# SCH_noobie-NFC_2024-11-30.net
KiCad netlist of a schematic drawn in EasyEDA
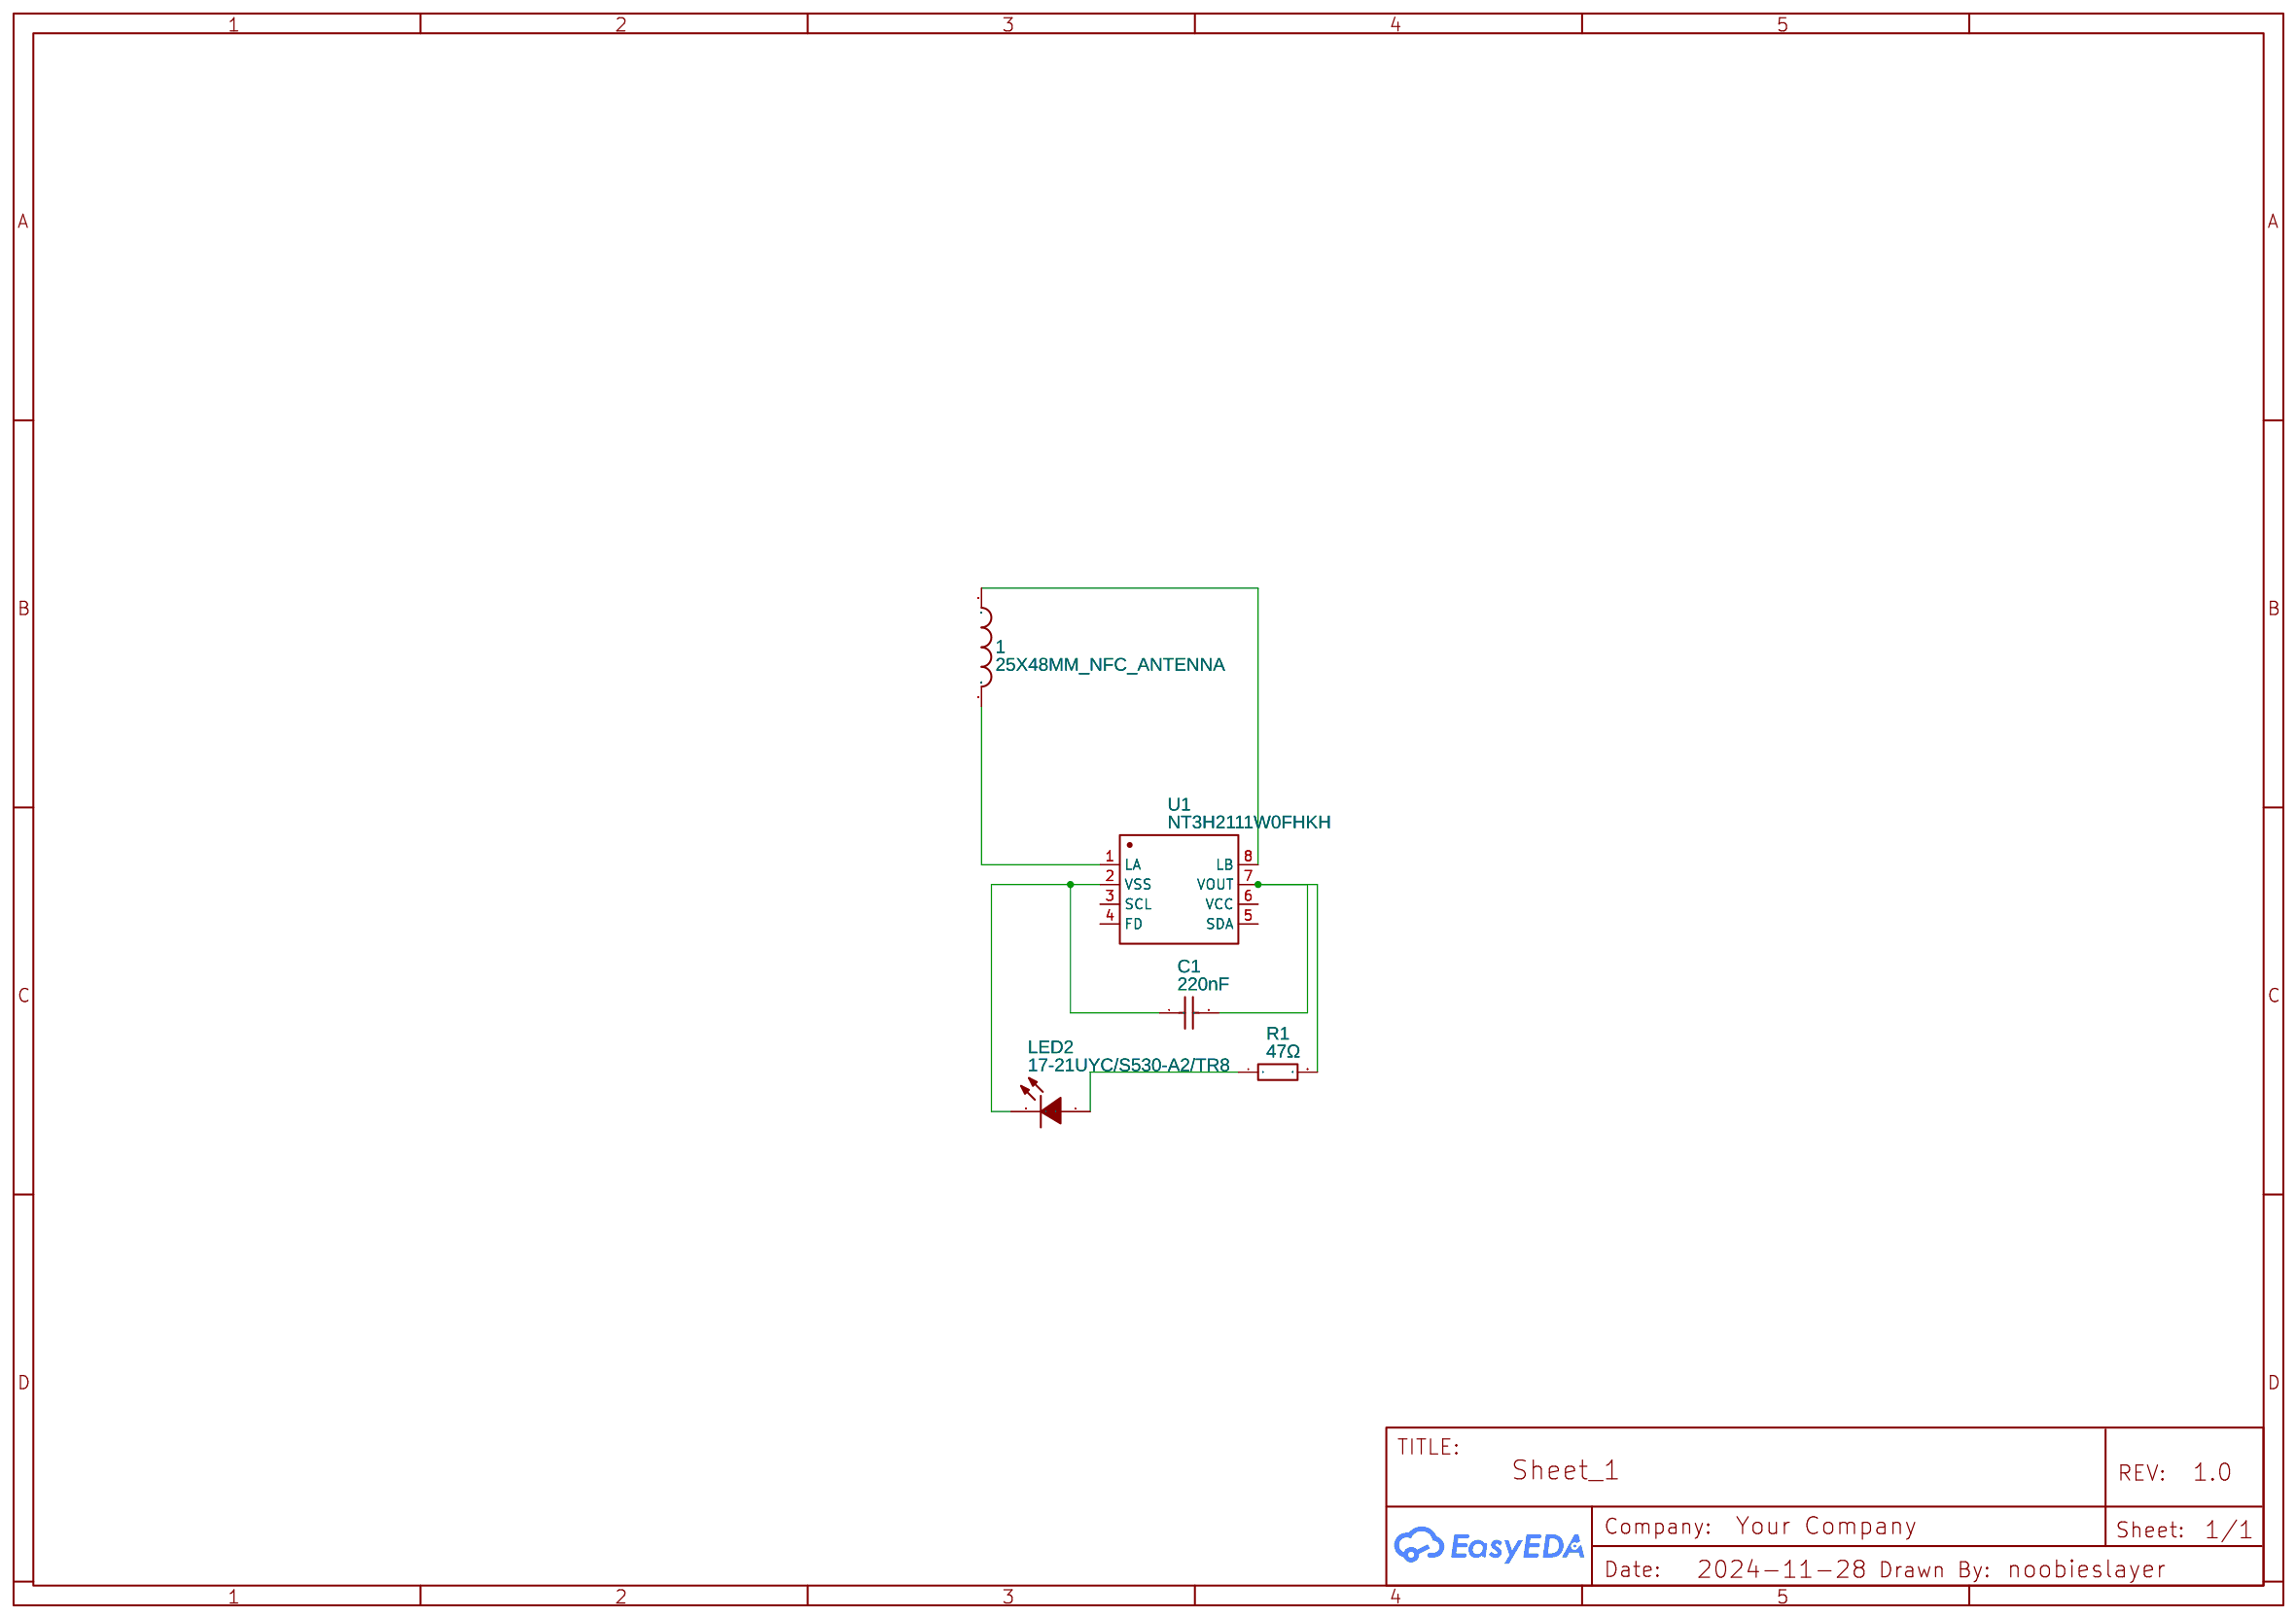
[diagram p0: schematic sheet]

(export (version "E")
  (design (tool "Eeschema 10.0.6"))
  (components
    (comp (ref "1") (value "25X48MM_NFC_ANTENNA") (libsource (lib "") (part "25X48MM_NFC_ANTENNA")))
    (comp (ref "C1")
      (value "220nF")
      (fields
        (field (name "Manufacturer Part") "CL10B224KA8NNNC")
        (field (name "Manufacturer") "SAMSUNG(三星)")
      )
      (libsource (lib "") (part "CL10B224KA8NNNC"))
    )
    (comp (ref "LED2")
      (value "17-21UYC/S530-A2/TR8")
      (fields (field (name "Manufacturer") "EVERLIGHT(亿光)"))
      (libsource (lib "") (part "17-21UYC/S530-A2/TR8"))
    )
    (comp (ref "R1")
      (value "47Ω")
      (fields
        (field (name "Manufacturer Part") "0603WAF470JT5E")
        (field (name "Manufacturer") "UNI-ROYAL(厚声)")
      )
      (libsource (lib "") (part "0603WAF470JT5E"))
    )
    (comp (ref "U1")
      (value "NT3H2111W0FHKH")
      (fields (field (name "Manufacturer") "NXP(恩智浦)"))
      (libsource (lib "") (part "NT3H2111W0FHKH"))
    )
  )
  (nets
    (net (code "1") (name "Net-(LED2-+)") (class "Default")
      (node (ref "LED2") (pin "1") (pinfunction "+_1") (pintype "unspecified"))
      (node (ref "R1") (pin "1") (pinfunction "1_1") (pintype "input"))
    )
    (net (code "2") (name "Net-(LED2--)") (class "Default")
      (node (ref "C1") (pin "1") (pinfunction "1_1") (pintype "input"))
      (node (ref "LED2") (pin "2") (pinfunction "-_2") (pintype "unspecified"))
      (node (ref "U1") (pin "2") (pinfunction "VSS_2") (pintype "unspecified"))
    )
    (net (code "3") (name "Net-(U1-LA)") (class "Default")
      (node (ref "1") (pin "P$2") (pinfunction "P$2_P$2") (pintype "bidirectional"))
      (node (ref "U1") (pin "1") (pinfunction "LA_1") (pintype "unspecified"))
    )
    (net (code "4") (name "Net-(U1-LB)") (class "Default")
      (node (ref "1") (pin "P$1") (pinfunction "P$1_P$1") (pintype "bidirectional"))
      (node (ref "U1") (pin "8") (pinfunction "LB_8") (pintype "unspecified"))
    )
    (net (code "5") (name "Net-(U1-VOUT)") (class "Default")
      (node (ref "C1") (pin "2") (pinfunction "2_2") (pintype "input"))
      (node (ref "R1") (pin "2") (pinfunction "2_2") (pintype "input"))
      (node (ref "U1") (pin "7") (pinfunction "VOUT_7") (pintype "unspecified"))
    )
    (net (code "6") (name "unconnected-(U1-FD-Pad4)") (class "Default")
      (node (ref "U1") (pin "4") (pinfunction "FD_4") (pintype "unspecified"))
    )
    (net (code "7") (name "unconnected-(U1-SCL-Pad3)") (class "Default")
      (node (ref "U1") (pin "3") (pinfunction "SCL_3") (pintype "unspecified"))
    )
    (net (code "8") (name "unconnected-(U1-SDA-Pad5)") (class "Default")
      (node (ref "U1") (pin "5") (pinfunction "SDA_5") (pintype "unspecified"))
    )
    (net (code "9") (name "unconnected-(U1-VCC-Pad6)") (class "Default")
      (node (ref "U1") (pin "6") (pinfunction "VCC_6") (pintype "unspecified"))
    )
  )
)
